# rf_rx.net
KiCad netlist of a schematic drawn in EAGLE
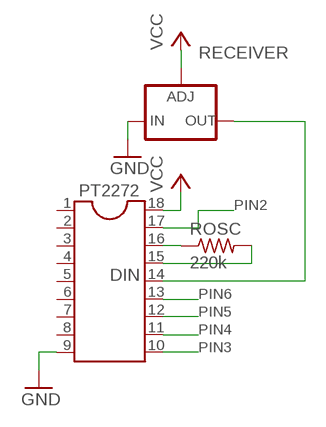
[diagram p0: schematic, sheet 1]

(export (version "E")
  (design (tool "Eeschema 10.0.6"))
  (components
    (comp (ref "PT2272")
      (value "DIL18")
      (footprint "eagle-import:DIL18")
      (libsource (lib "eagle-import") (part "DIL18"))
    )
    (comp (ref "RECEIVER")
      (value "LM337TS")
      (footprint "eagle-import:337TS")
      (libsource (lib "eagle-import") (part "LM337TS"))
    )
    (comp (ref "ROSC")
      (value "220k")
      (footprint "eagle-import:0204_5")
      (libsource (lib "eagle-import") (part "R-US_0204/5"))
    )
  )
  (nets
    (net (code "1") (name "/DIN") (class "Default")
      (node (ref "PT2272") (pin "14") (pinfunction "14_14") (pintype "passive"))
      (node (ref "RECEIVER") (pin "3") (pinfunction "OUT_3") (pintype "passive"))
    )
    (net (code "2") (name "/PIN2") (class "Default")
      (node (ref "PT2272") (pin "17") (pinfunction "17_17") (pintype "passive"))
    )
    (net (code "3") (name "/PIN3") (class "Default")
      (node (ref "PT2272") (pin "10") (pinfunction "10_10") (pintype "passive"))
    )
    (net (code "4") (name "/PIN4") (class "Default")
      (node (ref "PT2272") (pin "11") (pinfunction "11_11") (pintype "passive"))
    )
    (net (code "5") (name "/PIN5") (class "Default")
      (node (ref "PT2272") (pin "12") (pinfunction "12_12") (pintype "passive"))
    )
    (net (code "6") (name "/PIN6") (class "Default")
      (node (ref "PT2272") (pin "13") (pinfunction "13_13") (pintype "passive"))
    )
    (net (code "7") (name "GND") (class "Default")
      (node (ref "PT2272") (pin "9") (pinfunction "9_9") (pintype "passive"))
      (node (ref "RECEIVER") (pin "2") (pinfunction "IN_2") (pintype "input"))
    )
    (net (code "8") (name "Net-(PT2272-Pad15)") (class "Default")
      (node (ref "PT2272") (pin "15") (pinfunction "15_15") (pintype "passive"))
      (node (ref "ROSC") (pin "2") (pinfunction "2_2") (pintype "passive"))
    )
    (net (code "9") (name "Net-(PT2272-Pad16)") (class "Default")
      (node (ref "PT2272") (pin "16") (pinfunction "16_16") (pintype "passive"))
      (node (ref "ROSC") (pin "1") (pinfunction "1_1") (pintype "passive"))
    )
    (net (code "10") (name "VCC") (class "Default")
      (node (ref "PT2272") (pin "18") (pinfunction "18_18") (pintype "passive"))
      (node (ref "RECEIVER") (pin "1") (pinfunction "ADJ_1") (pintype "input"))
    )
    (net (code "11") (name "unconnected-(PT2272-Pad1)") (class "Default")
      (node (ref "PT2272") (pin "1") (pinfunction "1_1") (pintype "passive"))
    )
    (net (code "12") (name "unconnected-(PT2272-Pad2)") (class "Default")
      (node (ref "PT2272") (pin "2") (pinfunction "2_2") (pintype "passive"))
    )
    (net (code "13") (name "unconnected-(PT2272-Pad3)") (class "Default")
      (node (ref "PT2272") (pin "3") (pinfunction "3_3") (pintype "passive"))
    )
    (net (code "14") (name "unconnected-(PT2272-Pad4)") (class "Default")
      (node (ref "PT2272") (pin "4") (pinfunction "4_4") (pintype "passive"))
    )
    (net (code "15") (name "unconnected-(PT2272-Pad5)") (class "Default")
      (node (ref "PT2272") (pin "5") (pinfunction "5_5") (pintype "passive"))
    )
    (net (code "16") (name "unconnected-(PT2272-Pad6)") (class "Default")
      (node (ref "PT2272") (pin "6") (pinfunction "6_6") (pintype "passive"))
    )
    (net (code "17") (name "unconnected-(PT2272-Pad7)") (class "Default")
      (node (ref "PT2272") (pin "7") (pinfunction "7_7") (pintype "passive"))
    )
    (net (code "18") (name "unconnected-(PT2272-Pad8)") (class "Default")
      (node (ref "PT2272") (pin "8") (pinfunction "8_8") (pintype "passive"))
    )
  )
)
